# TUSB2036_PINOUT.net
KiCad netlist of a schematic drawn in Altium Designer
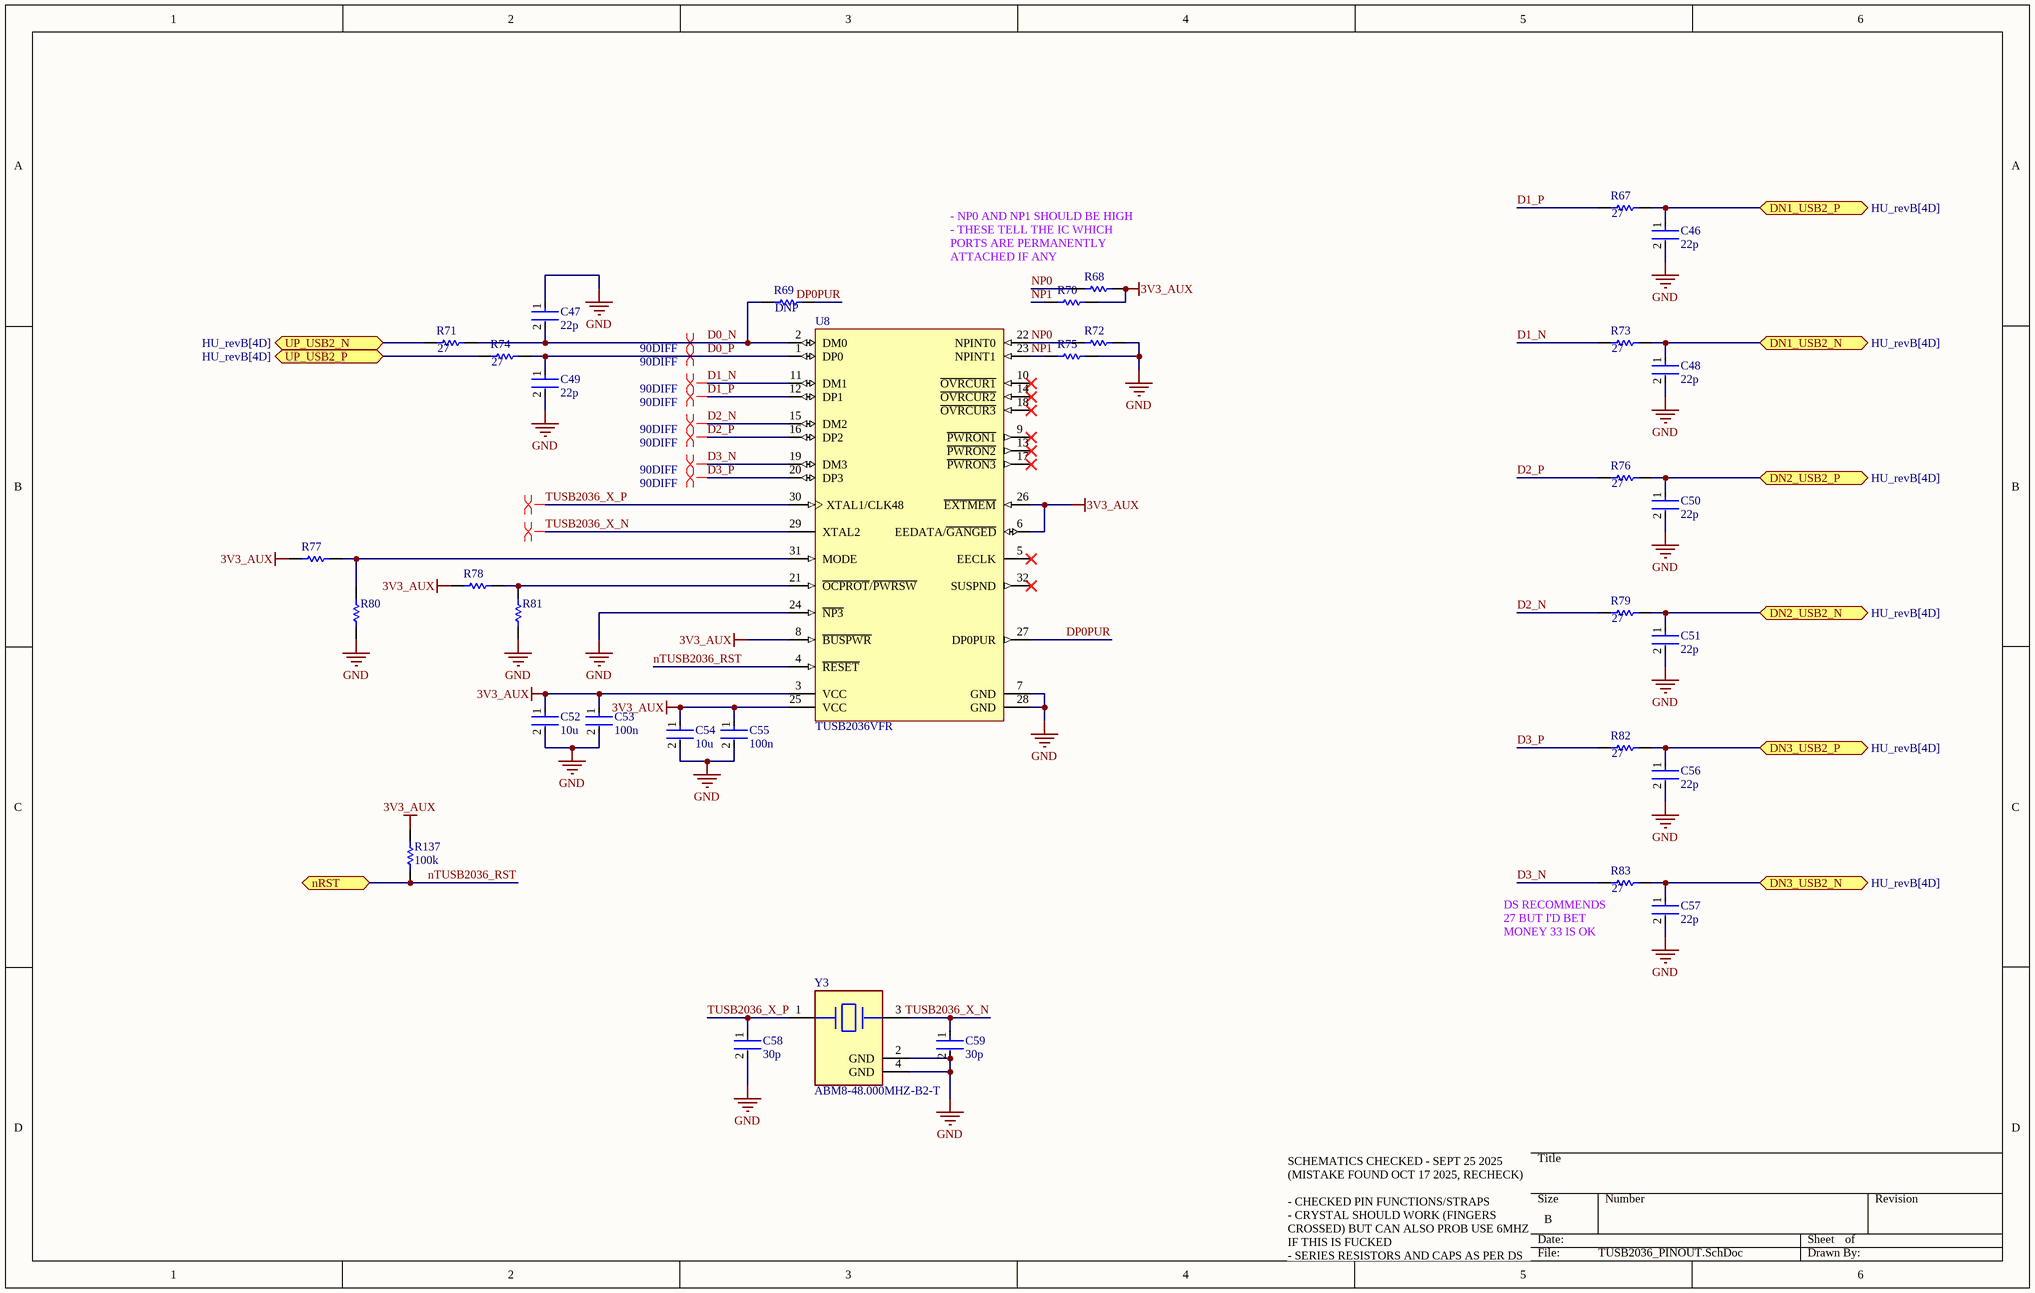
[diagram p0: TUSB2036_PINOUT.SchDoc]

(export (version "E")
  (design (tool "Eeschema 10.0.6"))
  (components
    (comp (ref "C46")
      (value "22p")
      (footprint "FP-0402-L_1_0_0_05-W_0_5-IPC_A")
      (description "LARGE PADS, 0402 CAP, CHANGE COMMENT TO MATCH REAL P/N")
      (libsource (lib "Space Concordia") (part "b4654b650e69147ec39a6b967a45e02"))
    )
    (comp (ref "C47")
      (value "22p")
      (footprint "FP-0402-L_1_0_0_05-W_0_5-IPC_A")
      (description "LARGE PADS, 0402 CAP, CHANGE COMMENT TO MATCH REAL P/N")
      (libsource (lib "Space Concordia") (part "b4654b650e69147ec39a6b967a45e02"))
    )
    (comp (ref "C48")
      (value "22p")
      (footprint "FP-0402-L_1_0_0_05-W_0_5-IPC_A")
      (description "LARGE PADS, 0402 CAP, CHANGE COMMENT TO MATCH REAL P/N")
      (libsource (lib "Space Concordia") (part "b4654b650e69147ec39a6b967a45e02"))
    )
    (comp (ref "C49")
      (value "22p")
      (footprint "FP-0402-L_1_0_0_05-W_0_5-IPC_A")
      (description "LARGE PADS, 0402 CAP, CHANGE COMMENT TO MATCH REAL P/N")
      (libsource (lib "Space Concordia") (part "b4654b650e69147ec39a6b967a45e02"))
    )
    (comp (ref "C50")
      (value "22p")
      (footprint "FP-0402-L_1_0_0_05-W_0_5-IPC_A")
      (description "LARGE PADS, 0402 CAP, CHANGE COMMENT TO MATCH REAL P/N")
      (libsource (lib "Space Concordia") (part "b4654b650e69147ec39a6b967a45e02"))
    )
    (comp (ref "C51")
      (value "22p")
      (footprint "FP-0402-L_1_0_0_05-W_0_5-IPC_A")
      (description "LARGE PADS, 0402 CAP, CHANGE COMMENT TO MATCH REAL P/N")
      (libsource (lib "Space Concordia") (part "b4654b650e69147ec39a6b967a45e02"))
    )
    (comp (ref "C52")
      (value "10u")
      (footprint "FP-0402-L_1_0_0_05-W_0_5-IPC_A")
      (description "LARGE PADS, 0402 CAP, CHANGE COMMENT TO MATCH REAL P/N")
      (libsource (lib "Space Concordia") (part "b4654b650e69147ec39a6b967a45e02"))
    )
    (comp (ref "C53")
      (value "100n")
      (footprint "FP-0402-L_1_0_0_05-W_0_5-IPC_A")
      (description "LARGE PADS, 0402 CAP, CHANGE COMMENT TO MATCH REAL P/N")
      (libsource (lib "Space Concordia") (part "b4654b650e69147ec39a6b967a45e02"))
    )
    (comp (ref "C54")
      (value "10u")
      (footprint "FP-0402-L_1_0_0_05-W_0_5-IPC_A")
      (description "LARGE PADS, 0402 CAP, CHANGE COMMENT TO MATCH REAL P/N")
      (libsource (lib "Space Concordia") (part "b4654b650e69147ec39a6b967a45e02"))
    )
    (comp (ref "C55")
      (value "100n")
      (footprint "FP-0402-L_1_0_0_05-W_0_5-IPC_A")
      (description "LARGE PADS, 0402 CAP, CHANGE COMMENT TO MATCH REAL P/N")
      (libsource (lib "Space Concordia") (part "b4654b650e69147ec39a6b967a45e02"))
    )
    (comp (ref "C56")
      (value "22p")
      (footprint "FP-0402-L_1_0_0_05-W_0_5-IPC_A")
      (description "LARGE PADS, 0402 CAP, CHANGE COMMENT TO MATCH REAL P/N")
      (libsource (lib "Space Concordia") (part "b4654b650e69147ec39a6b967a45e02"))
    )
    (comp (ref "C57")
      (value "22p")
      (footprint "FP-0402-L_1_0_0_05-W_0_5-IPC_A")
      (description "LARGE PADS, 0402 CAP, CHANGE COMMENT TO MATCH REAL P/N")
      (libsource (lib "Space Concordia") (part "b4654b650e69147ec39a6b967a45e02"))
    )
    (comp (ref "C58")
      (value "30p")
      (footprint "FP-0402-L_1_0_0_05-W_0_5-IPC_A")
      (description "LARGE PADS, 0402 CAP, CHANGE COMMENT TO MATCH REAL P/N")
      (libsource (lib "Space Concordia") (part "b4654b650e69147ec39a6b967a45e02"))
    )
    (comp (ref "C59")
      (value "30p")
      (footprint "FP-0402-L_1_0_0_05-W_0_5-IPC_A")
      (description "LARGE PADS, 0402 CAP, CHANGE COMMENT TO MATCH REAL P/N")
      (libsource (lib "Space Concordia") (part "b4654b650e69147ec39a6b967a45e02"))
    )
    (comp (ref "R67")
      (value "27")
      (footprint "R0603B")
      (description "Resistor")
      (libsource (lib "Space Concordia") (part "Resistor"))
    )
    (comp (ref "R68")
      (value "0402 JUMPER")
      (footprint "RESC1005X40X25ML05T05")
      (description "READ THE NAME")
      (libsource (lib "Space Concordia") (part "CMP-009-00206-2"))
    )
    (comp (ref "R69")
      (value "DNP")
      (footprint "R0603B")
      (description "Resistor")
      (libsource (lib "Space Concordia") (part "Resistor"))
    )
    (comp (ref "R70")
      (value "0402 JUMPER")
      (footprint "RESC1005X40X25ML05T05")
      (description "READ THE NAME")
      (libsource (lib "Space Concordia") (part "CMP-009-00206-2"))
    )
    (comp (ref "R71")
      (value "27")
      (footprint "R0603B")
      (description "Resistor")
      (libsource (lib "Space Concordia") (part "Resistor"))
    )
    (comp (ref "R72")
      (value "0402 JUMPER")
      (footprint "RESC1005X40X25ML05T05")
      (description "READ THE NAME")
      (libsource (lib "Space Concordia") (part "CMP-009-00206-2"))
    )
    (comp (ref "R73")
      (value "27")
      (footprint "R0603B")
      (description "Resistor")
      (libsource (lib "Space Concordia") (part "Resistor"))
    )
    (comp (ref "R74")
      (value "27")
      (footprint "R0603B")
      (description "Resistor")
      (libsource (lib "Space Concordia") (part "Resistor"))
    )
    (comp (ref "R75")
      (value "0402 JUMPER")
      (footprint "RESC1005X40X25ML05T05")
      (description "READ THE NAME")
      (libsource (lib "Space Concordia") (part "CMP-009-00206-2"))
    )
    (comp (ref "R76")
      (value "27")
      (footprint "R0603B")
      (description "Resistor")
      (libsource (lib "Space Concordia") (part "Resistor"))
    )
    (comp (ref "R77")
      (value "0402 JUMPER")
      (footprint "RESC1005X40X25ML05T05")
      (description "READ THE NAME")
      (libsource (lib "Space Concordia") (part "CMP-009-00206-2"))
    )
    (comp (ref "R78")
      (value "0402 JUMPER")
      (footprint "RESC1005X40X25ML05T05")
      (description "READ THE NAME")
      (libsource (lib "Space Concordia") (part "CMP-009-00206-2"))
    )
    (comp (ref "R79")
      (value "27")
      (footprint "R0603B")
      (description "Resistor")
      (libsource (lib "Space Concordia") (part "Resistor"))
    )
    (comp (ref "R80")
      (value "DNP")
      (footprint "RESC1005X40X25ML05T05")
      (description "READ THE NAME")
      (libsource (lib "Space Concordia") (part "CMP-009-00206-2"))
    )
    (comp (ref "R81")
      (value "DNP")
      (footprint "RESC1005X40X25ML05T05")
      (description "READ THE NAME")
      (libsource (lib "Space Concordia") (part "CMP-009-00206-2"))
    )
    (comp (ref "R82")
      (value "27")
      (footprint "R0603B")
      (description "Resistor")
      (libsource (lib "Space Concordia") (part "Resistor"))
    )
    (comp (ref "R83")
      (value "27")
      (footprint "R0603B")
      (description "Resistor")
      (libsource (lib "Space Concordia") (part "Resistor"))
    )
    (comp (ref "R137")
      (value "100k")
      (footprint "R0603B")
      (description "Resistor")
      (libsource (lib "Space Concordia") (part "Resistor"))
    )
    (comp (ref "U8")
      (value "TUSB2036VFR")
      (footprint "VF0032A_M")
      (fields (field (name "MANUFACTURER") "Texas Instruments"))
      (libsource (lib "Altium Content Vault") (part "TI-TUSB2036-LQFP_VF-32"))
    )
    (comp (ref "Y3")
      (value "ABM8-48.000MHZ-B2-T")
      (footprint "FP-ABM8-MFG")
      (description "Crystal 48MHz ±20ppm 18pF SMD-4 3.2mm x 2.5mm")
      (fields (field (name "TOLERANCE") "20ppm"))
      (libsource (lib "Altium Content Vault") (part "dfdb7f9a12507849fb681da9a70121c"))
    )
  )
  (nets
    (net (code "1") (name "/D0_N") (class "Default")
      (node (ref "C47") (pin "2") (pinfunction "2_2") (pintype "passive"))
      (node (ref "R69") (pin "2") (pinfunction "2_2") (pintype "passive"))
      (node (ref "R71") (pin "1") (pinfunction "1_1") (pintype "passive"))
      (node (ref "U8") (pin "2") (pinfunction "DM0_2") (pintype "bidirectional"))
    )
    (net (code "2") (name "/D0_P") (class "Default")
      (node (ref "C49") (pin "1") (pinfunction "1_1") (pintype "passive"))
      (node (ref "R74") (pin "1") (pinfunction "1_1") (pintype "passive"))
      (node (ref "U8") (pin "1") (pinfunction "DP0_1") (pintype "bidirectional"))
    )
    (net (code "3") (name "/D1_N") (class "Default")
      (node (ref "R73") (pin "2") (pinfunction "2_2") (pintype "passive"))
      (node (ref "U8") (pin "11") (pinfunction "DM1_11") (pintype "bidirectional"))
    )
    (net (code "4") (name "/D1_P") (class "Default")
      (node (ref "R67") (pin "2") (pinfunction "2_2") (pintype "passive"))
      (node (ref "U8") (pin "12") (pinfunction "DP1_12") (pintype "bidirectional"))
    )
    (net (code "5") (name "/D2_N") (class "Default")
      (node (ref "R79") (pin "2") (pinfunction "2_2") (pintype "passive"))
      (node (ref "U8") (pin "15") (pinfunction "DM2_15") (pintype "bidirectional"))
    )
    (net (code "6") (name "/D2_P") (class "Default")
      (node (ref "R76") (pin "2") (pinfunction "2_2") (pintype "passive"))
      (node (ref "U8") (pin "16") (pinfunction "DP2_16") (pintype "bidirectional"))
    )
    (net (code "7") (name "/D3_N") (class "Default")
      (node (ref "R83") (pin "2") (pinfunction "2_2") (pintype "passive"))
      (node (ref "U8") (pin "19") (pinfunction "DM3_19") (pintype "bidirectional"))
    )
    (net (code "8") (name "/D3_P") (class "Default")
      (node (ref "R82") (pin "2") (pinfunction "2_2") (pintype "passive"))
      (node (ref "U8") (pin "20") (pinfunction "DP3_20") (pintype "bidirectional"))
    )
    (net (code "9") (name "/DN1_USB2_N") (class "Default")
      (node (ref "C48") (pin "1") (pinfunction "1_1") (pintype "passive"))
      (node (ref "R73") (pin "1") (pinfunction "1_1") (pintype "passive"))
    )
    (net (code "10") (name "/DN1_USB2_P") (class "Default")
      (node (ref "C46") (pin "1") (pinfunction "1_1") (pintype "passive"))
      (node (ref "R67") (pin "1") (pinfunction "1_1") (pintype "passive"))
    )
    (net (code "11") (name "/DN2_USB2_N") (class "Default")
      (node (ref "C51") (pin "1") (pinfunction "1_1") (pintype "passive"))
      (node (ref "R79") (pin "1") (pinfunction "1_1") (pintype "passive"))
    )
    (net (code "12") (name "/DN2_USB2_P") (class "Default")
      (node (ref "C50") (pin "1") (pinfunction "1_1") (pintype "passive"))
      (node (ref "R76") (pin "1") (pinfunction "1_1") (pintype "passive"))
    )
    (net (code "13") (name "/DN3_USB2_N") (class "Default")
      (node (ref "C57") (pin "1") (pinfunction "1_1") (pintype "passive"))
      (node (ref "R83") (pin "1") (pinfunction "1_1") (pintype "passive"))
    )
    (net (code "14") (name "/DN3_USB2_P") (class "Default")
      (node (ref "C56") (pin "1") (pinfunction "1_1") (pintype "passive"))
      (node (ref "R82") (pin "1") (pinfunction "1_1") (pintype "passive"))
    )
    (net (code "15") (name "/DP0PUR") (class "Default")
      (node (ref "R69") (pin "1") (pinfunction "1_1") (pintype "passive"))
      (node (ref "U8") (pin "27") (pinfunction "DP0PUR_27") (pintype "output"))
    )
    (net (code "16") (name "/NP0") (class "Default")
      (node (ref "R68") (pin "1") (pinfunction "1_1") (pintype "passive"))
      (node (ref "R72") (pin "1") (pinfunction "1_1") (pintype "passive"))
      (node (ref "U8") (pin "22") (pinfunction "NPINT0_22") (pintype "input"))
    )
    (net (code "17") (name "/NP1") (class "Default")
      (node (ref "R70") (pin "1") (pinfunction "1_1") (pintype "passive"))
      (node (ref "R75") (pin "1") (pinfunction "1_1") (pintype "passive"))
      (node (ref "U8") (pin "23") (pinfunction "NPINT1_23") (pintype "input"))
    )
    (net (code "18") (name "/TUSB2036_X_N") (class "Default")
      (node (ref "C59") (pin "1") (pinfunction "1_1") (pintype "passive"))
      (node (ref "U8") (pin "29") (pinfunction "XTAL2_29") (pintype "passive"))
      (node (ref "Y3") (pin "3") (pinfunction "3_3") (pintype "passive"))
    )
    (net (code "19") (name "/TUSB2036_X_P") (class "Default")
      (node (ref "C58") (pin "1") (pinfunction "1_1") (pintype "passive"))
      (node (ref "U8") (pin "30") (pinfunction "XTAL1/CLK48_30") (pintype "input"))
      (node (ref "Y3") (pin "1") (pinfunction "1_1") (pintype "passive"))
    )
    (net (code "20") (name "/UP_USB2_N") (class "Default")
      (node (ref "R71") (pin "2") (pinfunction "2_2") (pintype "passive"))
    )
    (net (code "21") (name "/UP_USB2_P") (class "Default")
      (node (ref "R74") (pin "2") (pinfunction "2_2") (pintype "passive"))
    )
    (net (code "22") (name "/nTUSB2036_RST") (class "Default")
      (node (ref "R137") (pin "1") (pinfunction "1_1") (pintype "passive"))
      (node (ref "U8") (pin "4") (pinfunction "~{RESET}_4") (pintype "input"))
    )
    (net (code "23") (name "3V3_AUX") (class "Default")
      (node (ref "C52") (pin "1") (pinfunction "1_1") (pintype "passive"))
      (node (ref "C53") (pin "1") (pinfunction "1_1") (pintype "passive"))
      (node (ref "C54") (pin "1") (pinfunction "1_1") (pintype "passive"))
      (node (ref "C55") (pin "1") (pinfunction "1_1") (pintype "passive"))
      (node (ref "R137") (pin "2") (pinfunction "2_2") (pintype "passive"))
      (node (ref "R68") (pin "2") (pinfunction "2_2") (pintype "passive"))
      (node (ref "R70") (pin "2") (pinfunction "2_2") (pintype "passive"))
      (node (ref "R77") (pin "2") (pinfunction "2_2") (pintype "passive"))
      (node (ref "R78") (pin "2") (pinfunction "2_2") (pintype "passive"))
      (node (ref "U8") (pin "25") (pinfunction "VCC_25") (pintype "power_in"))
      (node (ref "U8") (pin "26") (pinfunction "~{EXTMEM}_26") (pintype "input"))
      (node (ref "U8") (pin "3") (pinfunction "VCC_3") (pintype "power_in"))
      (node (ref "U8") (pin "6") (pinfunction "EEDATA/~{GANGED}_6") (pintype "bidirectional"))
      (node (ref "U8") (pin "8") (pinfunction "~{BUSPWR}_8") (pintype "input"))
    )
    (net (code "24") (name "GND") (class "Default")
      (node (ref "C46") (pin "2") (pinfunction "2_2") (pintype "passive"))
      (node (ref "C47") (pin "1") (pinfunction "1_1") (pintype "passive"))
      (node (ref "C48") (pin "2") (pinfunction "2_2") (pintype "passive"))
      (node (ref "C49") (pin "2") (pinfunction "2_2") (pintype "passive"))
      (node (ref "C50") (pin "2") (pinfunction "2_2") (pintype "passive"))
      (node (ref "C51") (pin "2") (pinfunction "2_2") (pintype "passive"))
      (node (ref "C52") (pin "2") (pinfunction "2_2") (pintype "passive"))
      (node (ref "C53") (pin "2") (pinfunction "2_2") (pintype "passive"))
      (node (ref "C54") (pin "2") (pinfunction "2_2") (pintype "passive"))
      (node (ref "C55") (pin "2") (pinfunction "2_2") (pintype "passive"))
      (node (ref "C56") (pin "2") (pinfunction "2_2") (pintype "passive"))
      (node (ref "C57") (pin "2") (pinfunction "2_2") (pintype "passive"))
      (node (ref "C58") (pin "2") (pinfunction "2_2") (pintype "passive"))
      (node (ref "C59") (pin "2") (pinfunction "2_2") (pintype "passive"))
      (node (ref "R72") (pin "2") (pinfunction "2_2") (pintype "passive"))
      (node (ref "R75") (pin "2") (pinfunction "2_2") (pintype "passive"))
      (node (ref "R80") (pin "1") (pinfunction "1_1") (pintype "passive"))
      (node (ref "R81") (pin "1") (pinfunction "1_1") (pintype "passive"))
      (node (ref "U8") (pin "24") (pinfunction "~{NP3}_24") (pintype "input"))
      (node (ref "U8") (pin "28") (pinfunction "GND_28") (pintype "power_in"))
      (node (ref "U8") (pin "7") (pinfunction "GND_7") (pintype "power_in"))
      (node (ref "Y3") (pin "2") (pinfunction "GND_2") (pintype "power_in"))
      (node (ref "Y3") (pin "4") (pinfunction "GND_4") (pintype "power_in"))
    )
    (net (code "25") (name "Net-(U8-MODE)") (class "Default")
      (node (ref "R77") (pin "1") (pinfunction "1_1") (pintype "passive"))
      (node (ref "R80") (pin "2") (pinfunction "2_2") (pintype "passive"))
      (node (ref "U8") (pin "31") (pinfunction "MODE_31") (pintype "input"))
    )
    (net (code "26") (name "Net-(U8-~{OCPROT}{slash}~{PWRSW})") (class "Default")
      (node (ref "R78") (pin "1") (pinfunction "1_1") (pintype "passive"))
      (node (ref "R81") (pin "2") (pinfunction "2_2") (pintype "passive"))
      (node (ref "U8") (pin "21") (pinfunction "~{OCPROT}/~{PWRSW}_21") (pintype "input"))
    )
    (net (code "27") (name "unconnected-(U8-EECLK-Pad5)") (class "Default")
      (node (ref "U8") (pin "5") (pinfunction "EECLK_5") (pintype "tri_state+no_connect"))
    )
    (net (code "28") (name "unconnected-(U8-SUSPND-Pad32)") (class "Default")
      (node (ref "U8") (pin "32") (pinfunction "SUSPND_32") (pintype "output+no_connect"))
    )
    (net (code "29") (name "unconnected-(U8-~{OVRCUR1}-Pad10)") (class "Default")
      (node (ref "U8") (pin "10") (pinfunction "~{OVRCUR1}_10") (pintype "input+no_connect"))
    )
    (net (code "30") (name "unconnected-(U8-~{OVRCUR2}-Pad14)") (class "Default")
      (node (ref "U8") (pin "14") (pinfunction "~{OVRCUR2}_14") (pintype "input+no_connect"))
    )
    (net (code "31") (name "unconnected-(U8-~{OVRCUR3}-Pad18)") (class "Default")
      (node (ref "U8") (pin "18") (pinfunction "~{OVRCUR3}_18") (pintype "input+no_connect"))
    )
    (net (code "32") (name "unconnected-(U8-~{PWRON1}-Pad9)") (class "Default")
      (node (ref "U8") (pin "9") (pinfunction "~{PWRON1}_9") (pintype "output+no_connect"))
    )
    (net (code "33") (name "unconnected-(U8-~{PWRON2}-Pad13)") (class "Default")
      (node (ref "U8") (pin "13") (pinfunction "~{PWRON2}_13") (pintype "output+no_connect"))
    )
    (net (code "34") (name "unconnected-(U8-~{PWRON3}-Pad17)") (class "Default")
      (node (ref "U8") (pin "17") (pinfunction "~{PWRON3}_17") (pintype "output+no_connect"))
    )
  )
)
